# ng-beacon.net
KiCad netlist of a schematic drawn in EAGLE
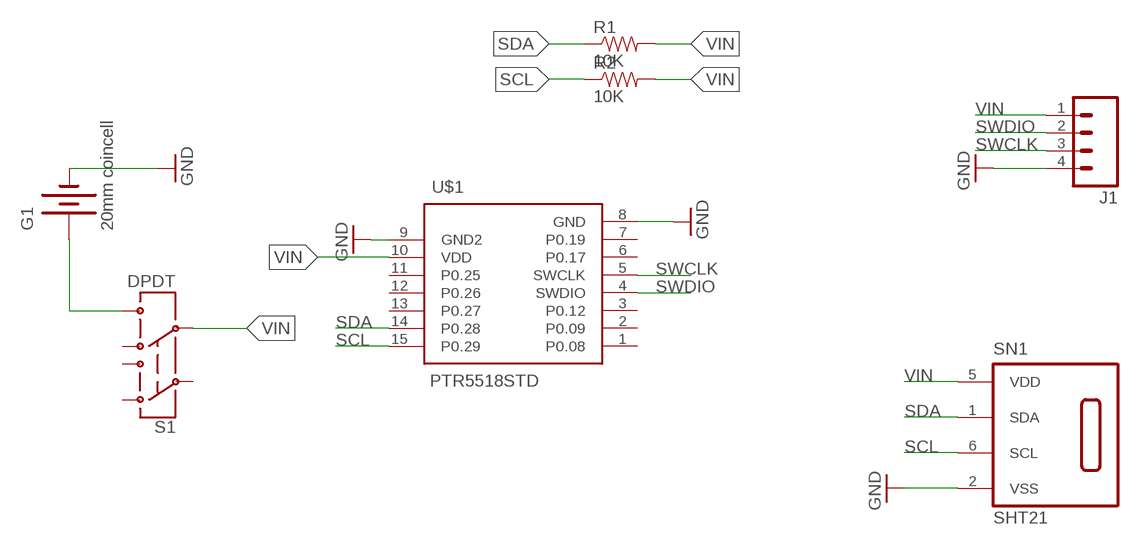
[diagram p0: schematic, sheet 1]

(export (version "E")
  (design (tool "Eeschema 10.0.6"))
  (components
    (comp (ref "G1")
      (value "20mm coincell")
      (footprint "eagle-import:BATTCON_20MM_4LEGS")
      (libsource (lib "eagle-import") (part "BATTERY20MM_4LEGS"))
    )
    (comp (ref "J1")
      (value "M04LOCK")
      (footprint "eagle-import:1X04_LOCK")
      (libsource (lib "eagle-import") (part "M04LOCK"))
    )
    (comp (ref "R1")
      (value "10K")
      (footprint "eagle-import:0603-RES")
      (libsource (lib "eagle-import") (part "10KOHM-1/10W-1%(0603)0603"))
    )
    (comp (ref "R2")
      (value "10K")
      (footprint "eagle-import:0603-RES")
      (libsource (lib "eagle-import") (part "10KOHM-1/10W-1%(0603)0603"))
    )
    (comp (ref "S1")
      (value "DPDT")
      (footprint "eagle-import:AYZ0202")
      (libsource (lib "eagle-import") (part "SWITCH-DPDTAYZ0202"))
    )
    (comp (ref "SN1")
      (value "SHT21")
      (footprint "eagle-import:DFN6_SHT")
      (libsource (lib "eagle-import") (part "SHT21"))
    )
    (comp (ref "U$1")
      (value "PTR5518STD")
      (footprint "eagle-import:PTR5518")
      (libsource (lib "eagle-import") (part "PTR5518STD"))
    )
  )
  (nets
    (net (code "1") (name "/SWCLK") (class "Default")
      (node (ref "J1") (pin "3") (pinfunction "3_3") (pintype "passive"))
      (node (ref "U$1") (pin "5") (pinfunction "SWCLK_5") (pintype "bidirectional"))
    )
    (net (code "2") (name "/SWDIO") (class "Default")
      (node (ref "J1") (pin "2") (pinfunction "2_2") (pintype "passive"))
      (node (ref "U$1") (pin "4") (pinfunction "SWDIO_4") (pintype "bidirectional"))
    )
    (net (code "3") (name "GND") (class "Default")
      (node (ref "G1") (pin "NEGATIVE") (pinfunction "-_NEGATIVE") (pintype "power_in"))
      (node (ref "J1") (pin "4") (pinfunction "4_4") (pintype "passive"))
      (node (ref "SN1") (pin "2") (pinfunction "VSS_2") (pintype "power_in"))
      (node (ref "U$1") (pin "8") (pinfunction "GND_8") (pintype "power_in"))
      (node (ref "U$1") (pin "9") (pinfunction "GND2_9") (pintype "power_in"))
    )
    (net (code "4") (name "Net-(G1-+-PadPOSITIVE@1)") (class "Default")
      (node (ref "G1") (pin "POSITIVE@1") (pinfunction "+_POSITIVE@1") (pintype "power_in"))
      (node (ref "G1") (pin "POSITIVE@2") (pinfunction "+_POSITIVE@2") (pintype "power_in"))
      (node (ref "G1") (pin "POSITIVE@3") (pinfunction "+_POSITIVE@3") (pintype "power_in"))
      (node (ref "G1") (pin "POSITIVE@4") (pinfunction "+_POSITIVE@4") (pintype "power_in"))
      (node (ref "S1") (pin "6") (pinfunction "6_6") (pintype "bidirectional"))
    )
    (net (code "5") (name "SCL") (class "Default")
      (node (ref "R2") (pin "1") (pinfunction "1_1") (pintype "passive"))
      (node (ref "SN1") (pin "6") (pinfunction "SCL_6") (pintype "bidirectional"))
      (node (ref "U$1") (pin "15") (pinfunction "P0.29_15") (pintype "bidirectional"))
    )
    (net (code "6") (name "SDA") (class "Default")
      (node (ref "R1") (pin "1") (pinfunction "1_1") (pintype "passive"))
      (node (ref "SN1") (pin "1") (pinfunction "SDA_1") (pintype "bidirectional"))
      (node (ref "U$1") (pin "14") (pinfunction "P0.28_14") (pintype "bidirectional"))
    )
    (net (code "7") (name "VIN") (class "Default")
      (node (ref "J1") (pin "1") (pinfunction "1_1") (pintype "passive"))
      (node (ref "R1") (pin "2") (pinfunction "2_2") (pintype "passive"))
      (node (ref "R2") (pin "2") (pinfunction "2_2") (pintype "passive"))
      (node (ref "S1") (pin "5") (pinfunction "5_5") (pintype "bidirectional"))
      (node (ref "SN1") (pin "5") (pinfunction "VDD_5") (pintype "power_in"))
      (node (ref "U$1") (pin "10") (pinfunction "VDD_10") (pintype "power_in"))
    )
    (net (code "8") (name "unconnected-(S1-Pad1)") (class "Default")
      (node (ref "S1") (pin "1") (pinfunction "1_1") (pintype "bidirectional"))
    )
    (net (code "9") (name "unconnected-(S1-Pad2)") (class "Default")
      (node (ref "S1") (pin "2") (pinfunction "2_2") (pintype "bidirectional"))
    )
    (net (code "10") (name "unconnected-(S1-Pad3)") (class "Default")
      (node (ref "S1") (pin "3") (pinfunction "3_3") (pintype "bidirectional"))
    )
    (net (code "11") (name "unconnected-(S1-Pad4)") (class "Default")
      (node (ref "S1") (pin "4") (pinfunction "4_4") (pintype "bidirectional"))
    )
    (net (code "12") (name "unconnected-(U$1-P0.08-Pad1)") (class "Default")
      (node (ref "U$1") (pin "1") (pinfunction "P0.08_1") (pintype "bidirectional"))
    )
    (net (code "13") (name "unconnected-(U$1-P0.09-Pad2)") (class "Default")
      (node (ref "U$1") (pin "2") (pinfunction "P0.09_2") (pintype "bidirectional"))
    )
    (net (code "14") (name "unconnected-(U$1-P0.12-Pad3)") (class "Default")
      (node (ref "U$1") (pin "3") (pinfunction "P0.12_3") (pintype "bidirectional"))
    )
    (net (code "15") (name "unconnected-(U$1-P0.17-Pad6)") (class "Default")
      (node (ref "U$1") (pin "6") (pinfunction "P0.17_6") (pintype "bidirectional"))
    )
    (net (code "16") (name "unconnected-(U$1-P0.19-Pad7)") (class "Default")
      (node (ref "U$1") (pin "7") (pinfunction "P0.19_7") (pintype "bidirectional"))
    )
    (net (code "17") (name "unconnected-(U$1-P0.25-Pad11)") (class "Default")
      (node (ref "U$1") (pin "11") (pinfunction "P0.25_11") (pintype "bidirectional"))
    )
    (net (code "18") (name "unconnected-(U$1-P0.26-Pad12)") (class "Default")
      (node (ref "U$1") (pin "12") (pinfunction "P0.26_12") (pintype "bidirectional"))
    )
    (net (code "19") (name "unconnected-(U$1-P0.27-Pad13)") (class "Default")
      (node (ref "U$1") (pin "13") (pinfunction "P0.27_13") (pintype "bidirectional"))
    )
  )
)
